# 02-MCU.net
KiCad netlist of a schematic drawn in Altium Designer
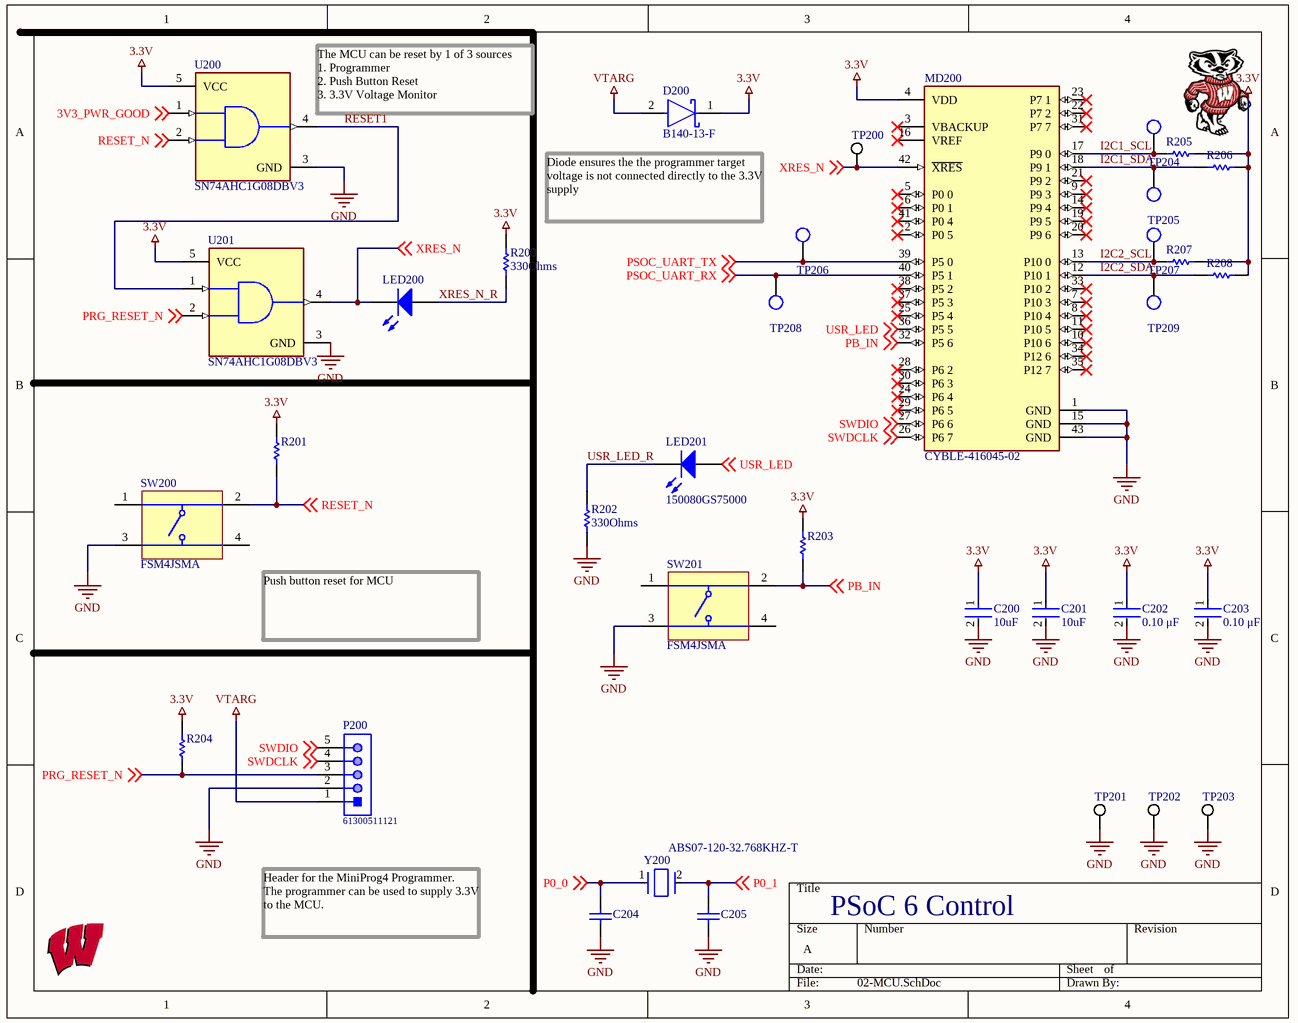
[diagram p0: 02-MCU.SchDoc]

(export (version "E")
  (design (tool "Eeschema 10.0.6"))
  (components
    (comp (ref "C200")
      (value "10uF")
      (footprint "FP-C0805C-DG-MFG")
      (description "CAP CER 10UF 10V X5R 0805")
      (fields (field (name "TOLERANCE") "10%") (field (name "MANUFACTURER PART NUMBER") "C0805C106K8PACTU"))
      (libsource (lib "Altium Content Vault") (part "11868f565c42a9108669ba33697ecf6"))
    )
    (comp (ref "C201")
      (value "10uF")
      (footprint "FP-C0805C-DG-MFG")
      (description "CAP CER 10UF 10V X5R 0805")
      (fields (field (name "TOLERANCE") "10%") (field (name "MANUFACTURER PART NUMBER") "C0805C106K8PACTU"))
      (libsource (lib "Altium Content Vault") (part "11868f565c42a9108669ba33697ecf6"))
    )
    (comp (ref "C202")
      (value "0.10 μF")
      (footprint "FP-C0805C-DN-MFG")
      (description "CAP CER 0.1UF 50V X7R 0805")
      (fields
        (field (name "MANUFACTURER PART NUMBER") "C0805C104K5RACTU")
        (field (name "MANUFACTURER") "KEMET")
      )
      (libsource (lib "Altium Content Vault") (part "b4654b650e69147ec39a6b967a45e02"))
    )
    (comp (ref "C203")
      (value "0.10 μF")
      (footprint "FP-C0805C-DN-MFG")
      (description "CAP CER 0.1UF 50V X7R 0805")
      (fields
        (field (name "MANUFACTURER PART NUMBER") "C0805C104K5RACTU")
        (field (name "MANUFACTURER") "KEMET")
      )
      (libsource (lib "Altium Content Vault") (part "b4654b650e69147ec39a6b967a45e02"))
    )
    (comp (ref "C204")
      (value "08055A6R0CAT2A")
      (footprint "CAPC2013X94X50LL20T25")
      (fields (field (name "MANUFACTURER") "AVX Interconnect / Elco"))
      (libsource (lib "Altium Content Vault") (part "CAP"))
    )
    (comp (ref "C205")
      (value "08055A6R0CAT2A")
      (footprint "CAPC2013X94X50LL20T25")
      (fields (field (name "MANUFACTURER") "AVX Interconnect / Elco"))
      (libsource (lib "Altium Content Vault") (part "CAP"))
    )
    (comp (ref "D200")
      (value "B140-13-F")
      (footprint "FP-SMA-MFG")
      (description "DIODE SCHOTTKY 40V 1A SMA")
      (libsource (lib "Altium Content Vault") (part "1d6ec82d83fb6aee721767c19dac4b9"))
    )
    (comp (ref "LED200")
      (value "150080RS75000")
      (footprint "0805_A")
      (description "SMD mono-color Chip LED, WL-SMCW, Red")
      (fields (field (name "MANUFACTURER") "Wuerth Elektronik"))
      (libsource (lib "Altium Content Vault") (part "WE-LED_K1A2-2"))
    )
    (comp (ref "LED201")
      (value "150080GS75000")
      (footprint "0805_A")
      (description "SMD mono-color Chip LED, WL-SMCW, Green")
      (fields (field (name "MANUFACTURER") "Wuerth Elektronik"))
      (libsource (lib "Altium Content Vault") (part "WE-LED_K1A2-2"))
    )
    (comp (ref "MD200")
      (value "CYBLE-416045-02")
      (footprint "FP-CYBLE-416045-02-MFG")
      (description "RF TXRX MOD BLUETOOTH TRACE ANT")
      (fields
        (field (name "OCTOPART") "https://octopart.com/cyble-416045-02-cypress+semiconductor-96386825")
        (field (name "MANUFACTURER") "Cypress Semiconductor")
      )
      (libsource (lib "Altium Content Vault") (part "10a29a4e77099fbb6f911efb04878b1"))
    )
    (comp (ref "P200")
      (value "61300511121")
      (footprint "61300511121")
      (description "THT Vertical Pin Header WR-PHD, Pitch 2.54 mm, Single Row, 5 pins")
      (fields (field (name "MANUFACTURER") "Wurth Elektronik") (field (name "PUBLISHER") "WurthElektronik"))
      (libsource (lib "Altium Content Vault") (part "WE-CN-1P-M-R5"))
    )
    (comp (ref "R200")
      (value "RC0805FR-07330RL")
      (footprint "RESC2013X60X35LL10T20")
      (description "Chip Resistor, 330 Ohm, +/- 1%, 125 mW, -55 to 155 degC, 0805 (2012 Metric), RoHS, Tape and Reel")
      (fields
        (field (name "MANUFACTURER") "Yageo")
        (field (name "TOLERANCE") "1%")
        (field (name "RESISTANCE") "330Ohms")
      )
      (libsource (lib "Altium Content Vault") (part "RES-2"))
    )
    (comp (ref "R201")
      (value "RC0805FR-0710KL")
      (footprint "RESC2013X60X35NL10T20")
      (description "Chip Resistor, 10 KOhm, +/- 1%, 0.125 W, -55 to 155 degC, 0805 (2012 Metric), RoHS, Tape and Reel")
      (fields (field (name "MANUFACTURER") "Yageo"))
      (libsource (lib "Altium Content Vault") (part "RES-2"))
    )
    (comp (ref "R202")
      (value "RC0805FR-07330RL")
      (footprint "RESC2013X60X35LL10T20")
      (description "Chip Resistor, 330 Ohm, +/- 1%, 125 mW, -55 to 155 degC, 0805 (2012 Metric), RoHS, Tape and Reel")
      (fields
        (field (name "MANUFACTURER") "Yageo")
        (field (name "TOLERANCE") "1%")
        (field (name "RESISTANCE") "330Ohms")
      )
      (libsource (lib "Altium Content Vault") (part "RES-2"))
    )
    (comp (ref "R203")
      (value "RC0805FR-0710KL")
      (footprint "RESC2013X60X35NL10T20")
      (description "Chip Resistor, 10 KOhm, +/- 1%, 0.125 W, -55 to 155 degC, 0805 (2012 Metric), RoHS, Tape and Reel")
      (fields (field (name "MANUFACTURER") "Yageo"))
      (libsource (lib "Altium Content Vault") (part "RES-2"))
    )
    (comp (ref "R204")
      (value "RC0805FR-0710KL")
      (footprint "RESC2013X60X35NL10T20")
      (description "Chip Resistor, 10 KOhm, +/- 1%, 0.125 W, -55 to 155 degC, 0805 (2012 Metric), RoHS, Tape and Reel")
      (fields (field (name "MANUFACTURER") "Yageo"))
      (libsource (lib "Altium Content Vault") (part "RES-2"))
    )
    (comp (ref "R205")
      (value "RC0805FR-0710KL")
      (footprint "RESC2013X60X35NL10T20")
      (description "Chip Resistor, 10 KOhm, +/- 1%, 0.125 W, -55 to 155 degC, 0805 (2012 Metric), RoHS, Tape and Reel")
      (fields (field (name "MANUFACTURER") "Yageo"))
      (libsource (lib "Altium Content Vault") (part "RES-2"))
    )
    (comp (ref "R206")
      (value "RC0805FR-0710KL")
      (footprint "RESC2013X60X35NL10T20")
      (description "Chip Resistor, 10 KOhm, +/- 1%, 0.125 W, -55 to 155 degC, 0805 (2012 Metric), RoHS, Tape and Reel")
      (fields (field (name "MANUFACTURER") "Yageo"))
      (libsource (lib "Altium Content Vault") (part "RES-2"))
    )
    (comp (ref "R207")
      (value "RC0805FR-0710KL")
      (footprint "RESC2013X60X35NL10T20")
      (description "Chip Resistor, 10 KOhm, +/- 1%, 0.125 W, -55 to 155 degC, 0805 (2012 Metric), RoHS, Tape and Reel")
      (fields (field (name "MANUFACTURER") "Yageo"))
      (libsource (lib "Altium Content Vault") (part "RES-2"))
    )
    (comp (ref "R208")
      (value "RC0805FR-0710KL")
      (footprint "RESC2013X60X35NL10T20")
      (description "Chip Resistor, 10 KOhm, +/- 1%, 0.125 W, -55 to 155 degC, 0805 (2012 Metric), RoHS, Tape and Reel")
      (fields (field (name "MANUFACTURER") "Yageo"))
      (libsource (lib "Altium Content Vault") (part "RES-2"))
    )
    (comp (ref "SW200")
      (value "FSM4JSMA")
      (footprint "TECO-FSM4JSMA_V")
      (description "Swicth, SPST, 24 V, -35 to 85 degC, 4-Pin SMD, RoHS, Tape and Reel")
      (fields (field (name "MANUFACTURER") "TE Connectivity"))
      (libsource (lib "Altium Content Vault") (part "SW-SPST-4_A"))
    )
    (comp (ref "SW201")
      (value "FSM4JSMA")
      (footprint "TECO-FSM4JSMA_V")
      (description "Swicth, SPST, 24 V, -35 to 85 degC, 4-Pin SMD, RoHS, Tape and Reel")
      (fields (field (name "MANUFACTURER") "TE Connectivity"))
      (libsource (lib "Altium Content Vault") (part "SW-SPST-4_A"))
    )
    (comp (ref "TP200")
      (value "5019")
      (footprint "KSTN-5019_V")
      (description "Test Point, 1 Position SMD, RoHS, Tape and Reel")
      (libsource (lib "Altium Content Vault") (part "TESTPOINT_WHITE"))
    )
    (comp (ref "TP201")
      (value "5019")
      (footprint "KSTN-5019_V")
      (description "Test Point, 1 Position SMD, RoHS, Tape and Reel")
      (libsource (lib "Altium Content Vault") (part "TESTPOINT_WHITE"))
    )
    (comp (ref "TP202")
      (value "5019")
      (footprint "KSTN-5019_V")
      (description "Test Point, 1 Position SMD, RoHS, Tape and Reel")
      (libsource (lib "Altium Content Vault") (part "TESTPOINT_WHITE"))
    )
    (comp (ref "TP203")
      (value "5019")
      (footprint "KSTN-5019_V")
      (description "Test Point, 1 Position SMD, RoHS, Tape and Reel")
      (libsource (lib "Altium Content Vault") (part "TESTPOINT_WHITE"))
    )
    (comp (ref "TP204")
      (value "TP_1206")
      (footprint "TP-SMC-1206")
      (description "Test Point SMD 1206")
      (fields
        (field (name "MANUFACTURER") "TE Connectivity (Tyco Electronics)")
        (field (name "MANUFACTURER PART NUMBER") "1625854-1")
      )
      (libsource (lib "base-board") (part "TP_1206"))
    )
    (comp (ref "TP205")
      (value "TP_1206")
      (footprint "TP-SMC-1206")
      (description "Test Point SMD 1206")
      (fields
        (field (name "MANUFACTURER") "TE Connectivity (Tyco Electronics)")
        (field (name "MANUFACTURER PART NUMBER") "1625854-1")
      )
      (libsource (lib "base-board") (part "TP_1206"))
    )
    (comp (ref "TP206")
      (value "TP_1206")
      (footprint "TP-SMC-1206")
      (description "Test Point SMD 1206")
      (fields
        (field (name "MANUFACTURER") "TE Connectivity (Tyco Electronics)")
        (field (name "MANUFACTURER PART NUMBER") "1625854-1")
      )
      (libsource (lib "base-board") (part "TP_1206"))
    )
    (comp (ref "TP207")
      (value "TP_1206")
      (footprint "TP-SMC-1206")
      (description "Test Point SMD 1206")
      (fields
        (field (name "MANUFACTURER") "TE Connectivity (Tyco Electronics)")
        (field (name "MANUFACTURER PART NUMBER") "1625854-1")
      )
      (libsource (lib "base-board") (part "TP_1206"))
    )
    (comp (ref "TP208")
      (value "TP_1206")
      (footprint "TP-SMC-1206")
      (description "Test Point SMD 1206")
      (fields
        (field (name "MANUFACTURER") "TE Connectivity (Tyco Electronics)")
        (field (name "MANUFACTURER PART NUMBER") "1625854-1")
      )
      (libsource (lib "base-board") (part "TP_1206"))
    )
    (comp (ref "TP209")
      (value "TP_1206")
      (footprint "TP-SMC-1206")
      (description "Test Point SMD 1206")
      (fields
        (field (name "MANUFACTURER") "TE Connectivity (Tyco Electronics)")
        (field (name "MANUFACTURER PART NUMBER") "1625854-1")
      )
      (libsource (lib "base-board") (part "TP_1206"))
    )
    (comp (ref "U200")
      (value "SN74AHC1G08DBV3")
      (footprint "FP-DBV0005A-IPC_C")
      (description "IC GATE AND 1CH 2-INP SOT23-5")
      (libsource (lib "Altium Content Vault") (part "675e79b427d6219a5295bf943425e1c"))
    )
    (comp (ref "U201")
      (value "SN74AHC1G08DBV3")
      (footprint "FP-DBV0005A-IPC_C")
      (description "IC GATE AND 1CH 2-INP SOT23-5")
      (libsource (lib "Altium Content Vault") (part "675e79b427d6219a5295bf943425e1c"))
    )
    (comp (ref "Y200")
      (value "ABS07-120-32.768KHZ-T")
      (footprint "FP-ABS07-120-MFG")
      (description "CRYSTAL 32.7680KHZ 6PF SMD")
      (fields (field (name "TOLERANCE") "20ppm"))
      (libsource (lib "Altium Content Vault") (part "c23a69dc6c9e2f18f2079038eb95dd1"))
    )
  )
  (nets
    (net (code "1") (name "/I2C1_SCL") (class "Default")
      (node (ref "MD200") (pin "17") (pinfunction "P9_0_17") (pintype "bidirectional"))
      (node (ref "R205") (pin "2") (pinfunction "2_2") (pintype "passive"))
      (node (ref "TP204") (pin "1") (pintype "passive"))
    )
    (net (code "2") (name "/I2C1_SDA") (class "Default")
      (node (ref "MD200") (pin "18") (pinfunction "P9_1_18") (pintype "bidirectional"))
      (node (ref "R206") (pin "2") (pinfunction "2_2") (pintype "passive"))
      (node (ref "TP205") (pin "1") (pintype "passive"))
    )
    (net (code "3") (name "/I2C2_SCL") (class "Default")
      (node (ref "MD200") (pin "13") (pinfunction "P10_0_13") (pintype "bidirectional"))
      (node (ref "R207") (pin "2") (pinfunction "2_2") (pintype "passive"))
      (node (ref "TP207") (pin "1") (pintype "passive"))
    )
    (net (code "4") (name "/I2C2_SDA") (class "Default")
      (node (ref "MD200") (pin "12") (pinfunction "P10_1_12") (pintype "bidirectional"))
      (node (ref "R208") (pin "2") (pinfunction "2_2") (pintype "passive"))
      (node (ref "TP209") (pin "1") (pintype "passive"))
    )
    (net (code "5") (name "/RESET1") (class "Default")
      (node (ref "U200") (pin "4") (pinfunction "Y_4") (pintype "output"))
      (node (ref "U201") (pin "1") (pinfunction "A_1") (pintype "input"))
    )
    (net (code "6") (name "/USR_LED_R") (class "Default")
      (node (ref "LED201") (pin "1") (pinfunction "K_1") (pintype "passive"))
      (node (ref "R202") (pin "2") (pinfunction "2_2") (pintype "passive"))
    )
    (net (code "7") (name "/XRES_N_R") (class "Default")
      (node (ref "LED200") (pin "2") (pinfunction "A_2") (pintype "passive"))
      (node (ref "R200") (pin "1") (pinfunction "1_1") (pintype "passive"))
    )
    (net (code "8") (name "3.3V") (class "Default")
      (node (ref "C200") (pin "1") (pinfunction "1_1") (pintype "passive"))
      (node (ref "C201") (pin "1") (pinfunction "1_1") (pintype "passive"))
      (node (ref "C202") (pin "1") (pinfunction "1_1") (pintype "passive"))
      (node (ref "C203") (pin "1") (pinfunction "1_1") (pintype "passive"))
      (node (ref "D200") (pin "1") (pinfunction "C_1") (pintype "passive"))
      (node (ref "MD200") (pin "4") (pinfunction "VDD_4") (pintype "power_in"))
      (node (ref "R200") (pin "2") (pinfunction "2_2") (pintype "passive"))
      (node (ref "R201") (pin "2") (pinfunction "2_2") (pintype "passive"))
      (node (ref "R203") (pin "2") (pinfunction "2_2") (pintype "passive"))
      (node (ref "R204") (pin "2") (pinfunction "2_2") (pintype "passive"))
      (node (ref "R205") (pin "1") (pinfunction "1_1") (pintype "passive"))
      (node (ref "R206") (pin "1") (pinfunction "1_1") (pintype "passive"))
      (node (ref "R207") (pin "1") (pinfunction "1_1") (pintype "passive"))
      (node (ref "R208") (pin "1") (pinfunction "1_1") (pintype "passive"))
      (node (ref "U200") (pin "5") (pinfunction "VCC_5") (pintype "power_in"))
      (node (ref "U201") (pin "5") (pinfunction "VCC_5") (pintype "power_in"))
    )
    (net (code "9") (name "3V3_PWR_GOOD") (class "Default")
      (node (ref "U200") (pin "1") (pinfunction "A_1") (pintype "input"))
    )
    (net (code "10") (name "GND") (class "Default")
      (node (ref "C200") (pin "2") (pinfunction "2_2") (pintype "passive"))
      (node (ref "C201") (pin "2") (pinfunction "2_2") (pintype "passive"))
      (node (ref "C202") (pin "2") (pinfunction "2_2") (pintype "passive"))
      (node (ref "C203") (pin "2") (pinfunction "2_2") (pintype "passive"))
      (node (ref "C204") (pin "1") (pinfunction "1_1") (pintype "passive"))
      (node (ref "C205") (pin "1") (pinfunction "1_1") (pintype "passive"))
      (node (ref "MD200") (pin "1") (pinfunction "GND_1") (pintype "power_in"))
      (node (ref "MD200") (pin "15") (pinfunction "GND_15") (pintype "power_in"))
      (node (ref "MD200") (pin "43") (pinfunction "GND_43") (pintype "power_in"))
      (node (ref "P200") (pin "2") (pinfunction "2_2") (pintype "passive"))
      (node (ref "R202") (pin "1") (pinfunction "1_1") (pintype "passive"))
      (node (ref "SW200") (pin "3") (pinfunction "3_3") (pintype "passive"))
      (node (ref "SW201") (pin "3") (pinfunction "3_3") (pintype "passive"))
      (node (ref "TP201") (pin "1") (pinfunction "1_1") (pintype "passive"))
      (node (ref "TP202") (pin "1") (pinfunction "1_1") (pintype "passive"))
      (node (ref "TP203") (pin "1") (pinfunction "1_1") (pintype "passive"))
      (node (ref "U200") (pin "3") (pinfunction "GND_3") (pintype "power_in"))
      (node (ref "U201") (pin "3") (pinfunction "GND_3") (pintype "power_in"))
    )
    (net (code "11") (name "P0_0") (class "Default")
      (node (ref "C204") (pin "2") (pinfunction "2_2") (pintype "passive"))
      (node (ref "Y200") (pin "1") (pinfunction "1_1") (pintype "passive"))
    )
    (net (code "12") (name "P0_1") (class "Default")
      (node (ref "C205") (pin "2") (pinfunction "2_2") (pintype "passive"))
      (node (ref "Y200") (pin "2") (pinfunction "2_2") (pintype "passive"))
    )
    (net (code "13") (name "PB_IN") (class "Default")
      (node (ref "MD200") (pin "32") (pinfunction "P5_6_32") (pintype "bidirectional"))
      (node (ref "R203") (pin "1") (pinfunction "1_1") (pintype "passive"))
      (node (ref "SW201") (pin "2") (pinfunction "2_2") (pintype "passive"))
    )
    (net (code "14") (name "PRG_RESET_N") (class "Default")
      (node (ref "P200") (pin "3") (pinfunction "3_3") (pintype "passive"))
      (node (ref "R204") (pin "1") (pinfunction "1_1") (pintype "passive"))
      (node (ref "U201") (pin "2") (pinfunction "B_2") (pintype "input"))
    )
    (net (code "15") (name "PSOC_UART_RX") (class "Default")
      (node (ref "MD200") (pin "40") (pinfunction "P5_1_40") (pintype "bidirectional"))
      (node (ref "TP208") (pin "1") (pintype "passive"))
    )
    (net (code "16") (name "PSOC_UART_TX") (class "Default")
      (node (ref "MD200") (pin "39") (pinfunction "P5_0_39") (pintype "bidirectional"))
      (node (ref "TP206") (pin "1") (pintype "passive"))
    )
    (net (code "17") (name "RESET_N") (class "Default")
      (node (ref "R201") (pin "1") (pinfunction "1_1") (pintype "passive"))
      (node (ref "SW200") (pin "2") (pinfunction "2_2") (pintype "passive"))
      (node (ref "U200") (pin "2") (pinfunction "B_2") (pintype "input"))
    )
    (net (code "18") (name "SWDCLK") (class "Default")
      (node (ref "MD200") (pin "26") (pinfunction "P6_7_26") (pintype "bidirectional"))
      (node (ref "P200") (pin "4") (pinfunction "4_4") (pintype "passive"))
    )
    (net (code "19") (name "SWDIO") (class "Default")
      (node (ref "MD200") (pin "27") (pinfunction "P6_6_27") (pintype "bidirectional"))
      (node (ref "P200") (pin "5") (pinfunction "5_5") (pintype "passive"))
    )
    (net (code "20") (name "USR_LED") (class "Default")
      (node (ref "LED201") (pin "2") (pinfunction "A_2") (pintype "passive"))
      (node (ref "MD200") (pin "36") (pinfunction "P5_5_36") (pintype "bidirectional"))
    )
    (net (code "21") (name "VTARG") (class "Default")
      (node (ref "D200") (pin "2") (pinfunction "A_2") (pintype "passive"))
      (node (ref "P200") (pin "1") (pinfunction "1_1") (pintype "passive"))
    )
    (net (code "22") (name "XRES_N") (class "Default")
      (node (ref "LED200") (pin "1") (pinfunction "K_1") (pintype "passive"))
      (node (ref "MD200") (pin "42") (pinfunction "~{XRES}_42") (pintype "input"))
      (node (ref "TP200") (pin "1") (pinfunction "1_1") (pintype "passive"))
      (node (ref "U201") (pin "4") (pinfunction "Y_4") (pintype "output"))
    )
    (net (code "23") (name "unconnected-(MD200-P0_0-Pad5)") (class "Default")
      (node (ref "MD200") (pin "5") (pinfunction "P0_0_5") (pintype "bidirectional+no_connect"))
    )
    (net (code "24") (name "unconnected-(MD200-P0_1-Pad6)") (class "Default")
      (node (ref "MD200") (pin "6") (pinfunction "P0_1_6") (pintype "bidirectional+no_connect"))
    )
    (net (code "25") (name "unconnected-(MD200-P0_4-Pad41)") (class "Default")
      (node (ref "MD200") (pin "41") (pinfunction "P0_4_41") (pintype "bidirectional+no_connect"))
    )
    (net (code "26") (name "unconnected-(MD200-P0_5-Pad2)") (class "Default")
      (node (ref "MD200") (pin "2") (pinfunction "P0_5_2") (pintype "bidirectional+no_connect"))
    )
    (net (code "27") (name "unconnected-(MD200-P5_2-Pad38)") (class "Default")
      (node (ref "MD200") (pin "38") (pinfunction "P5_2_38") (pintype "bidirectional+no_connect"))
    )
    (net (code "28") (name "unconnected-(MD200-P5_3-Pad37)") (class "Default")
      (node (ref "MD200") (pin "37") (pinfunction "P5_3_37") (pintype "bidirectional+no_connect"))
    )
    (net (code "29") (name "unconnected-(MD200-P5_4-Pad25)") (class "Default")
      (node (ref "MD200") (pin "25") (pinfunction "P5_4_25") (pintype "bidirectional+no_connect"))
    )
    (net (code "30") (name "unconnected-(MD200-P6_2-Pad28)") (class "Default")
      (node (ref "MD200") (pin "28") (pinfunction "P6_2_28") (pintype "bidirectional+no_connect"))
    )
    (net (code "31") (name "unconnected-(MD200-P6_3-Pad30)") (class "Default")
      (node (ref "MD200") (pin "30") (pinfunction "P6_3_30") (pintype "bidirectional+no_connect"))
    )
    (net (code "32") (name "unconnected-(MD200-P6_4-Pad24)") (class "Default")
      (node (ref "MD200") (pin "24") (pinfunction "P6_4_24") (pintype "bidirectional+no_connect"))
    )
    (net (code "33") (name "unconnected-(MD200-P6_5-Pad29)") (class "Default")
      (node (ref "MD200") (pin "29") (pinfunction "P6_5_29") (pintype "bidirectional+no_connect"))
    )
    (net (code "34") (name "unconnected-(MD200-P7_1-Pad23)") (class "Default")
      (node (ref "MD200") (pin "23") (pinfunction "P7_1_23") (pintype "bidirectional+no_connect"))
    )
    (net (code "35") (name "unconnected-(MD200-P7_2-Pad22)") (class "Default")
      (node (ref "MD200") (pin "22") (pinfunction "P7_2_22") (pintype "bidirectional+no_connect"))
    )
    (net (code "36") (name "unconnected-(MD200-P7_7-Pad31)") (class "Default")
      (node (ref "MD200") (pin "31") (pinfunction "P7_7_31") (pintype "bidirectional+no_connect"))
    )
    (net (code "37") (name "unconnected-(MD200-P9_2-Pad21)") (class "Default")
      (node (ref "MD200") (pin "21") (pinfunction "P9_2_21") (pintype "bidirectional+no_connect"))
    )
    (net (code "38") (name "unconnected-(MD200-P9_3-Pad9)") (class "Default")
      (node (ref "MD200") (pin "9") (pinfunction "P9_3_9") (pintype "bidirectional+no_connect"))
    )
    (net (code "39") (name "unconnected-(MD200-P9_4-Pad14)") (class "Default")
      (node (ref "MD200") (pin "14") (pinfunction "P9_4_14") (pintype "bidirectional+no_connect"))
    )
    (net (code "40") (name "unconnected-(MD200-P9_5-Pad19)") (class "Default")
      (node (ref "MD200") (pin "19") (pinfunction "P9_5_19") (pintype "bidirectional+no_connect"))
    )
    (net (code "41") (name "unconnected-(MD200-P9_6-Pad20)") (class "Default")
      (node (ref "MD200") (pin "20") (pinfunction "P9_6_20") (pintype "bidirectional+no_connect"))
    )
    (net (code "42") (name "unconnected-(MD200-P10_2-Pad33)") (class "Default")
      (node (ref "MD200") (pin "33") (pinfunction "P10_2_33") (pintype "bidirectional+no_connect"))
    )
    (net (code "43") (name "unconnected-(MD200-P10_3-Pad7)") (class "Default")
      (node (ref "MD200") (pin "7") (pinfunction "P10_3_7") (pintype "bidirectional+no_connect"))
    )
    (net (code "44") (name "unconnected-(MD200-P10_4-Pad8)") (class "Default")
      (node (ref "MD200") (pin "8") (pinfunction "P10_4_8") (pintype "bidirectional+no_connect"))
    )
    (net (code "45") (name "unconnected-(MD200-P10_5-Pad11)") (class "Default")
      (node (ref "MD200") (pin "11") (pinfunction "P10_5_11") (pintype "bidirectional+no_connect"))
    )
    (net (code "46") (name "unconnected-(MD200-P10_6-Pad10)") (class "Default")
      (node (ref "MD200") (pin "10") (pinfunction "P10_6_10") (pintype "bidirectional+no_connect"))
    )
    (net (code "47") (name "unconnected-(MD200-P12_6-Pad34)") (class "Default")
      (node (ref "MD200") (pin "34") (pinfunction "P12_6_34") (pintype "bidirectional+no_connect"))
    )
    (net (code "48") (name "unconnected-(MD200-P12_7-Pad35)") (class "Default")
      (node (ref "MD200") (pin "35") (pinfunction "P12_7_35") (pintype "bidirectional+no_connect"))
    )
    (net (code "49") (name "unconnected-(MD200-VBACKUP-Pad3)") (class "Default")
      (node (ref "MD200") (pin "3") (pinfunction "VBACKUP_3") (pintype "power_in+no_connect"))
    )
    (net (code "50") (name "unconnected-(MD200-VREF-Pad16)") (class "Default")
      (node (ref "MD200") (pin "16") (pinfunction "VREF_16") (pintype "power_in+no_connect"))
    )
    (net (code "51") (name "unconnected-(SW200-Pad1)") (class "Default")
      (node (ref "SW200") (pin "1") (pinfunction "1_1") (pintype "passive"))
    )
    (net (code "52") (name "unconnected-(SW200-Pad4)") (class "Default")
      (node (ref "SW200") (pin "4") (pinfunction "4_4") (pintype "passive"))
    )
    (net (code "53") (name "unconnected-(SW201-Pad1)") (class "Default")
      (node (ref "SW201") (pin "1") (pinfunction "1_1") (pintype "passive"))
    )
    (net (code "54") (name "unconnected-(SW201-Pad4)") (class "Default")
      (node (ref "SW201") (pin "4") (pinfunction "4_4") (pintype "passive"))
    )
  )
)
